# SCH_Record-wav_2025-12-09_1.net
KiCad netlist of a schematic drawn in EasyEDA
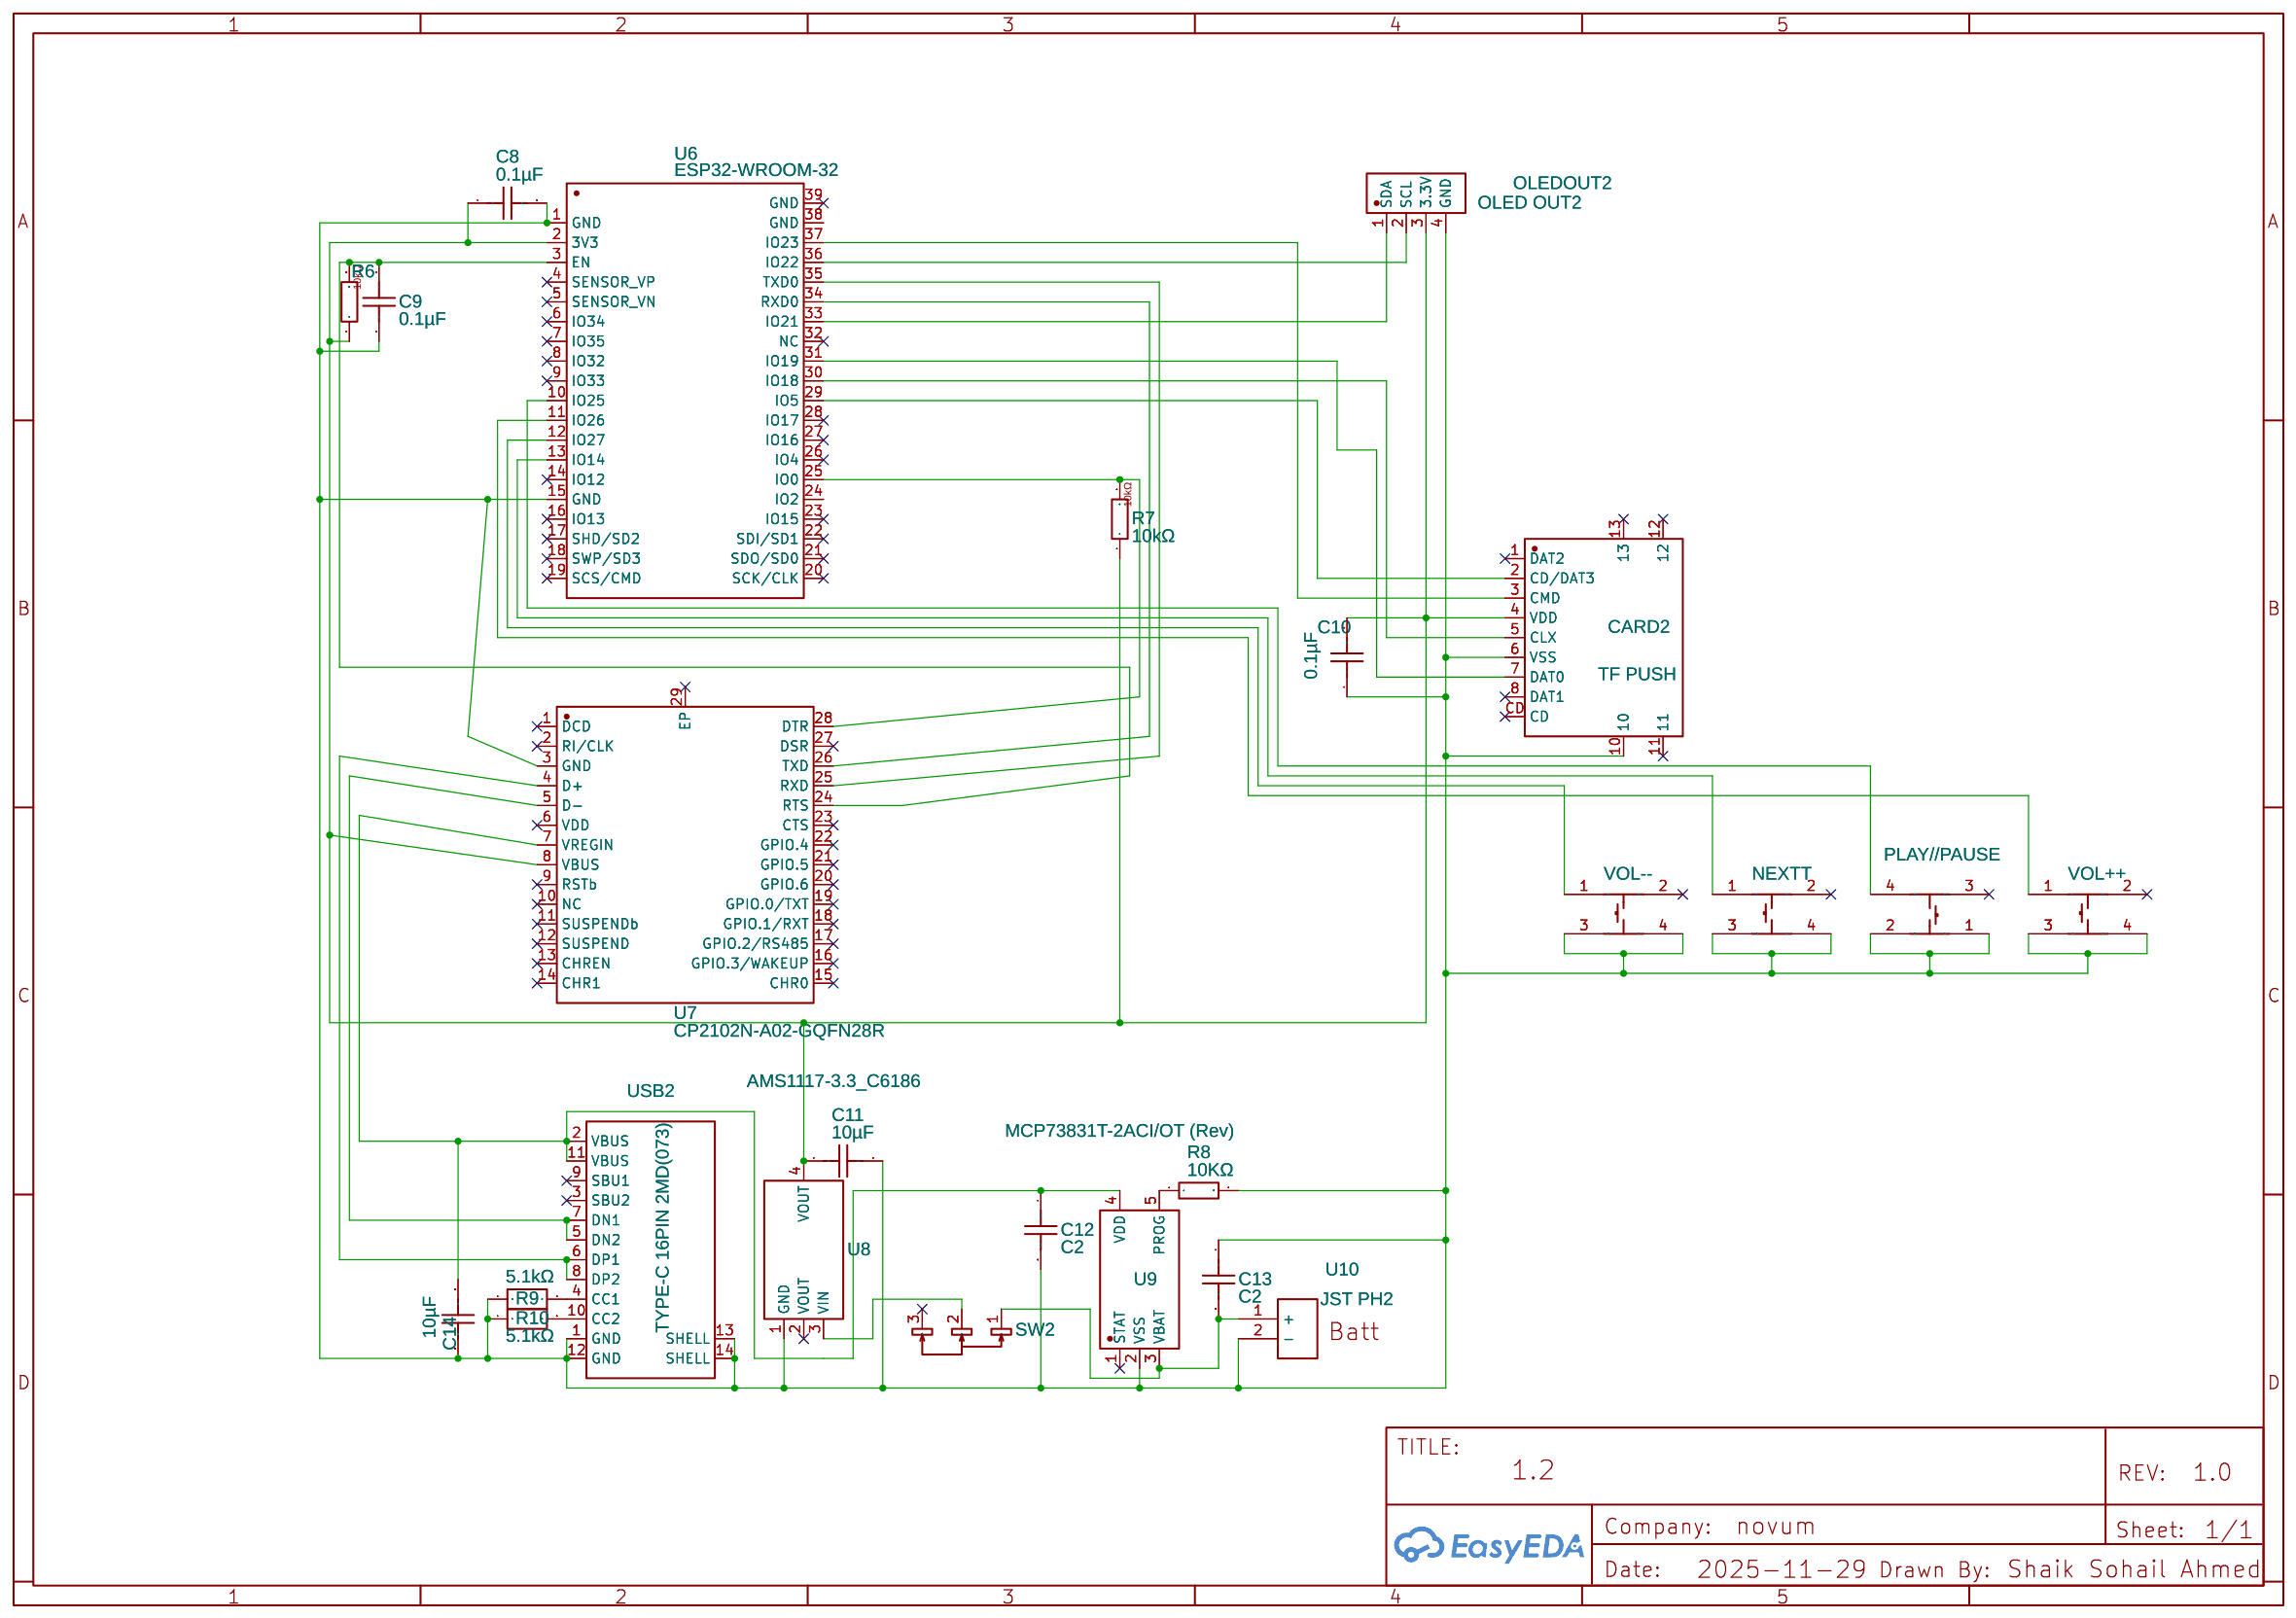
[diagram p0: schematic sheet]

(export (version "E")
  (design (tool "Eeschema 10.0.6"))
  (components
    (comp (ref "C8")
      (value "0.1µF")
      (fields (field (name "Manufacturer Part") "GRM152R60J104ME19D") (field (name "Manufacturer") "muRata"))
      (libsource (lib "") (part "0.1µF_1"))
    )
    (comp (ref "C9")
      (value "0.1µF")
      (fields (field (name "Manufacturer Part") "GRM152R60J104ME19D") (field (name "Manufacturer") "muRata"))
      (libsource (lib "") (part "0.1µF"))
    )
    (comp (ref "C10")
      (value "0.1µF")
      (fields (field (name "Manufacturer Part") "GRM152R60J104ME19D") (field (name "Manufacturer") "muRata"))
      (libsource (lib "") (part "0.1µF"))
    )
    (comp (ref "C11")
      (value "10µF")
      (fields
        (field (name "Manufacturer Part") "CL10A106MA8NRNC")
        (field (name "Manufacturer") "Samsung Electro-Mechanics")
      )
      (libsource (lib "") (part "CL10A106MA8NRNC_1"))
    )
    (comp (ref "C12")
      (value "C2")
      (fields (field (name "Manufacturer Part") "08053C105JAT2A") (field (name "Manufacturer") "KYOCERA AVX"))
      (libsource (lib "") (part "08053C105JAT2A"))
    )
    (comp (ref "C13")
      (value "C2")
      (fields (field (name "Manufacturer Part") "08053C105JAT2A") (field (name "Manufacturer") "KYOCERA AVX"))
      (libsource (lib "") (part "08053C105JAT2A"))
    )
    (comp (ref "C14")
      (value "10µF")
      (fields
        (field (name "Manufacturer Part") "CL10A106MA8NRNC")
        (field (name "Manufacturer") "Samsung Electro-Mechanics")
      )
      (libsource (lib "") (part "CL10A106MA8NRNC"))
    )
    (comp (ref "CARD2")
      (value "TF PUSH")
      (fields (field (name "Manufacturer") "SHOU HAN(首韩)"))
      (libsource (lib "") (part "TF PUSH"))
    )
    (comp (ref "NEXTT")
      (value "TS-1002S-07026C")
      (fields (field (name "Manufacturer") "XUNPU(讯普)"))
      (libsource (lib "") (part "TS-1002S-07026C_2"))
    )
    (comp (ref "OLEDOUT2") (value "OLED OUT2") (libsource (lib "") (part "Solder_Pad_4")))
    (comp (ref "PLAY//PAUSE")
      (value "TS-1002S-07026C")
      (fields (field (name "Manufacturer") "XUNPU(讯普)"))
      (libsource (lib "") (part "TS-1002S-07026C_3"))
    )
    (comp (ref "R6") (value "10kΩ") (libsource (lib "") (part "10kΩ")))
    (comp (ref "R7") (value "10kΩ") (libsource (lib "") (part "10kΩ")))
    (comp (ref "R8")
      (value "10KΩ")
      (fields (field (name "Manufacturer Part") "CFR0W4J0103A50") (field (name "Manufacturer") "UniOhm"))
      (libsource (lib "") (part "10KΩ"))
    )
    (comp (ref "R9")
      (value "5.1kΩ")
      (fields (field (name "Manufacturer Part") "FRC1206F5101TS") (field (name "Manufacturer") "FOJAN(富捷)"))
      (libsource (lib "") (part "5.1KΩ 1/4W ±1% SMD"))
    )
    (comp (ref "R10")
      (value "5.1kΩ")
      (fields (field (name "Manufacturer Part") "FRC1206F5101TS") (field (name "Manufacturer") "FOJAN(富捷)"))
      (libsource (lib "") (part "5.1KΩ 1/4W ±1% SMD"))
    )
    (comp (ref "SW2")
      (value "MST-12D18G4 SPDT SLIDE SWITCH")
      (fields
        (field (name "Manufacturer Part") "MST-12D18G4 SPDT Slide Switch")
        (field (name "Manufacturer") "SHOU HAN(首韩)")
      )
      (libsource (lib "") (part "MST-12D18G4 SPDT SLIDE SWITCH"))
    )
    (comp (ref "U6")
      (value "ESP32-WROOM-32")
      (fields
        (field (name "Manufacturer Part") "ESP32-WROOM-32-N4")
        (field (name "Manufacturer") "ESPRESSIF(乐鑫)")
      )
      (libsource (lib "") (part "ESP32-WROOM-32"))
    )
    (comp (ref "U7")
      (value "CP2102N-A02-GQFN28R")
      (fields (field (name "Manufacturer") "SKYWORKS/SILICON LABS(芯科)"))
      (libsource (lib "") (part "CP2102N-A02-GQFN28R"))
    )
    (comp (ref "U8")
      (value "AMS1117-3.3_C6186")
      (fields (field (name "Manufacturer Part") "AMS1117-3.3") (field (name "Manufacturer") "AMS"))
      (libsource (lib "") (part "AMS1117-3.3_C6186"))
    )
    (comp (ref "U9")
      (value "MCP73831T-2ACI/OT (Rev)")
      (fields
        (field (name "Manufacturer Part") "MCP73831T-2ACI/OT")
        (field (name "Manufacturer") "MICROCHIP(美国微芯)")
      )
      (libsource (lib "") (part "MCP73831T-2ACI/OT (Rev)"))
    )
    (comp (ref "U10") (value "JST PH2") (libsource (lib "") (part "JST PH2")))
    (comp (ref "USB2")
      (value "TYPE-C 16PIN 2MD(073)")
      (fields (field (name "Manufacturer") "SHOU HAN(首韩)"))
      (libsource (lib "") (part "TYPE-C 16PIN 2MD(073)"))
    )
    (comp (ref "VOL++")
      (value "TS-1002S-07026C")
      (fields (field (name "Manufacturer") "XUNPU(讯普)"))
      (libsource (lib "") (part "TS-1002S-07026C_1"))
    )
    (comp (ref "VOL--")
      (value "TS-1002S-07026C")
      (fields (field (name "Manufacturer") "XUNPU(讯普)"))
      (libsource (lib "") (part "TS-1002S-07026C"))
    )
  )
  (nets
    (net (code "1") (name "Net-(CARD2-CD{slash}DAT3)") (class "Default")
      (node (ref "CARD2") (pin "2") (pinfunction "CD/DAT3_2") (pintype "unspecified"))
      (node (ref "U6") (pin "29") (pinfunction "IO5_29") (pintype "unspecified"))
    )
    (net (code "2") (name "Net-(CARD2-CLX)") (class "Default")
      (node (ref "CARD2") (pin "5") (pinfunction "CLX_5") (pintype "unspecified"))
      (node (ref "U6") (pin "30") (pinfunction "IO18_30") (pintype "unspecified"))
    )
    (net (code "3") (name "Net-(CARD2-CMD)") (class "Default")
      (node (ref "CARD2") (pin "3") (pinfunction "CMD_3") (pintype "unspecified"))
      (node (ref "U6") (pin "37") (pinfunction "IO23_37") (pintype "unspecified"))
    )
    (net (code "4") (name "Net-(CARD2-DAT0)") (class "Default")
      (node (ref "CARD2") (pin "7") (pinfunction "DAT0_7") (pintype "unspecified"))
      (node (ref "U6") (pin "31") (pinfunction "IO19_31") (pintype "unspecified"))
    )
    (net (code "5") (name "Net-(CARD2-VDD)") (class "Default")
      (node (ref "C10") (pin "2") (pinfunction "2_2") (pintype "unspecified"))
      (node (ref "C11") (pin "1") (pinfunction "1_1") (pintype "unspecified"))
      (node (ref "C8") (pin "1") (pinfunction "1_1") (pintype "unspecified"))
      (node (ref "CARD2") (pin "4") (pinfunction "VDD_4") (pintype "unspecified"))
      (node (ref "OLEDOUT2") (pin "3") (pinfunction "3.3V_3") (pintype "unspecified"))
      (node (ref "R6") (pin "1") (pinfunction "1_1") (pintype "unspecified"))
      (node (ref "R7") (pin "1") (pinfunction "1_1") (pintype "unspecified"))
      (node (ref "U6") (pin "2") (pinfunction "3V3_2") (pintype "unspecified"))
      (node (ref "U7") (pin "8") (pinfunction "VBUS_8") (pintype "unspecified"))
      (node (ref "U8") (pin "4") (pinfunction "VOUT_4") (pintype "unspecified"))
    )
    (net (code "6") (name "Net-(CARD2-VSS)") (class "Default")
      (node (ref "C10") (pin "1") (pinfunction "1_1") (pintype "unspecified"))
      (node (ref "C11") (pin "2") (pinfunction "2_2") (pintype "unspecified"))
      (node (ref "C12") (pin "2") (pinfunction "2_2") (pintype "unspecified"))
      (node (ref "C13") (pin "1") (pinfunction "1_1") (pintype "unspecified"))
      (node (ref "C14") (pin "2") (pinfunction "2_2") (pintype "unspecified"))
      (node (ref "C8") (pin "2") (pinfunction "2_2") (pintype "unspecified"))
      (node (ref "C9") (pin "1") (pinfunction "1_1") (pintype "unspecified"))
      (node (ref "CARD2") (pin "10") (pinfunction "10_10") (pintype "unspecified"))
      (node (ref "CARD2") (pin "6") (pinfunction "VSS_6") (pintype "unspecified"))
      (node (ref "NEXTT") (pin "3") (pinfunction "3_3") (pintype "unspecified"))
      (node (ref "NEXTT") (pin "4") (pinfunction "4_4") (pintype "unspecified"))
      (node (ref "OLEDOUT2") (pin "4") (pinfunction "GND_4") (pintype "unspecified"))
      (node (ref "PLAY//PAUSE") (pin "1") (pinfunction "1_1") (pintype "unspecified"))
      (node (ref "PLAY//PAUSE") (pin "2") (pinfunction "2_2") (pintype "unspecified"))
      (node (ref "R10") (pin "1") (pinfunction "1_1") (pintype "unspecified"))
      (node (ref "R8") (pin "2") (pinfunction "2_2") (pintype "input"))
      (node (ref "R9") (pin "1") (pinfunction "1_1") (pintype "unspecified"))
      (node (ref "U10") (pin "2") (pinfunction "-_2") (pintype "unspecified"))
      (node (ref "U6") (pin "1") (pinfunction "GND_1") (pintype "unspecified"))
      (node (ref "U6") (pin "15") (pinfunction "GND_15") (pintype "unspecified"))
      (node (ref "U7") (pin "3") (pinfunction "GND_3") (pintype "unspecified"))
      (node (ref "U8") (pin "1") (pinfunction "GND_1") (pintype "unspecified"))
      (node (ref "U9") (pin "2") (pinfunction "VSS_2") (pintype "unspecified"))
      (node (ref "USB2") (pin "1") (pinfunction "GND_1") (pintype "unspecified"))
      (node (ref "USB2") (pin "12") (pinfunction "GND_12") (pintype "unspecified"))
      (node (ref "USB2") (pin "13") (pinfunction "SHELL_13") (pintype "unspecified"))
      (node (ref "USB2") (pin "14") (pinfunction "SHELL_14") (pintype "unspecified"))
      (node (ref "VOL++") (pin "3") (pinfunction "3_3") (pintype "unspecified"))
      (node (ref "VOL++") (pin "4") (pinfunction "4_4") (pintype "unspecified"))
      (node (ref "VOL--") (pin "3") (pinfunction "3_3") (pintype "unspecified"))
      (node (ref "VOL--") (pin "4") (pinfunction "4_4") (pintype "unspecified"))
    )
    (net (code "7") (name "Net-(OLEDOUT2-SCL)") (class "Default")
      (node (ref "OLEDOUT2") (pin "2") (pinfunction "SCL_2") (pintype "unspecified"))
      (node (ref "U6") (pin "36") (pinfunction "IO22_36") (pintype "unspecified"))
    )
    (net (code "8") (name "Net-(OLEDOUT2-SDA)") (class "Default")
      (node (ref "OLEDOUT2") (pin "1") (pinfunction "SDA_1") (pintype "unspecified"))
      (node (ref "U6") (pin "33") (pinfunction "IO21_33") (pintype "unspecified"))
    )
    (net (code "9") (name "Net-(U6-EN)") (class "Default")
      (node (ref "C9") (pin "2") (pinfunction "2_2") (pintype "unspecified"))
      (node (ref "R6") (pin "2") (pinfunction "2_2") (pintype "unspecified"))
      (node (ref "U6") (pin "3") (pinfunction "EN_3") (pintype "unspecified"))
      (node (ref "U7") (pin "24") (pinfunction "RTS_24") (pintype "unspecified"))
    )
    (net (code "10") (name "Net-(U6-IO0)") (class "Default")
      (node (ref "R7") (pin "2") (pinfunction "2_2") (pintype "unspecified"))
      (node (ref "U6") (pin "25") (pinfunction "IO0_25") (pintype "unspecified"))
      (node (ref "U7") (pin "28") (pinfunction "DTR_28") (pintype "unspecified"))
    )
    (net (code "11") (name "Net-(U6-IO14)") (class "Default")
      (node (ref "NEXTT") (pin "1") (pinfunction "1_1") (pintype "unspecified"))
      (node (ref "U6") (pin "13") (pinfunction "IO14_13") (pintype "unspecified"))
    )
    (net (code "12") (name "Net-(U6-IO25)") (class "Default")
      (node (ref "PLAY//PAUSE") (pin "4") (pinfunction "4_4") (pintype "unspecified"))
      (node (ref "U6") (pin "10") (pinfunction "IO25_10") (pintype "unspecified"))
    )
    (net (code "13") (name "Net-(U6-IO26)") (class "Default")
      (node (ref "U6") (pin "11") (pinfunction "IO26_11") (pintype "unspecified"))
      (node (ref "VOL++") (pin "1") (pinfunction "1_1") (pintype "unspecified"))
    )
    (net (code "14") (name "Net-(U6-IO27)") (class "Default")
      (node (ref "U6") (pin "12") (pinfunction "IO27_12") (pintype "unspecified"))
      (node (ref "VOL--") (pin "1") (pinfunction "1_1") (pintype "unspecified"))
    )
    (net (code "15") (name "Net-(U6-RXD0)") (class "Default")
      (node (ref "U6") (pin "34") (pinfunction "RXD0_34") (pintype "unspecified"))
      (node (ref "U7") (pin "26") (pinfunction "TXD_26") (pintype "unspecified"))
    )
    (net (code "16") (name "Net-(U6-TXD0)") (class "Default")
      (node (ref "U6") (pin "35") (pinfunction "TXD0_35") (pintype "unspecified"))
      (node (ref "U7") (pin "25") (pinfunction "RXD_25") (pintype "unspecified"))
    )
    (net (code "17") (name "Net-(U7-D+)") (class "Default")
      (node (ref "U7") (pin "4") (pinfunction "D+_4") (pintype "unspecified"))
      (node (ref "USB2") (pin "6") (pinfunction "DP1_6") (pintype "unspecified"))
      (node (ref "USB2") (pin "8") (pinfunction "DP2_8") (pintype "unspecified"))
    )
    (net (code "18") (name "Net-(U7-D-)") (class "Default")
      (node (ref "U7") (pin "5") (pinfunction "D-_5") (pintype "unspecified"))
      (node (ref "USB2") (pin "5") (pinfunction "DN2_5") (pintype "unspecified"))
      (node (ref "USB2") (pin "7") (pinfunction "DN1_7") (pintype "unspecified"))
    )
    (net (code "19") (name "Net-(U7-VREGIN)") (class "Default")
      (node (ref "C12") (pin "1") (pinfunction "1_1") (pintype "unspecified"))
      (node (ref "C14") (pin "1") (pinfunction "1_1") (pintype "unspecified"))
      (node (ref "U7") (pin "7") (pinfunction "VREGIN_7") (pintype "unspecified"))
      (node (ref "U9") (pin "4") (pinfunction "VDD_4") (pintype "unspecified"))
      (node (ref "USB2") (pin "11") (pinfunction "VBUS_11") (pintype "unspecified"))
      (node (ref "USB2") (pin "2") (pinfunction "VBUS_2") (pintype "unspecified"))
    )
    (net (code "20") (name "Net-(U8-VIN)") (class "Default")
      (node (ref "SW2") (pin "2") (pinfunction "2_2") (pintype "unspecified"))
      (node (ref "U8") (pin "3") (pinfunction "VIN_3") (pintype "unspecified"))
    )
    (net (code "21") (name "Net-(U9-PROG)") (class "Default")
      (node (ref "R8") (pin "1") (pinfunction "1_1") (pintype "input"))
      (node (ref "U9") (pin "5") (pinfunction "PROG_5") (pintype "unspecified"))
    )
    (net (code "22") (name "Net-(U10-+)") (class "Default")
      (node (ref "C13") (pin "2") (pinfunction "2_2") (pintype "unspecified"))
      (node (ref "SW2") (pin "1") (pinfunction "1_1") (pintype "unspecified"))
      (node (ref "U10") (pin "1") (pinfunction "+_1") (pintype "unspecified"))
      (node (ref "U9") (pin "3") (pinfunction "VBAT_3") (pintype "unspecified"))
    )
    (net (code "23") (name "Net-(USB2-CC1)") (class "Default")
      (node (ref "R9") (pin "2") (pinfunction "2_2") (pintype "unspecified"))
      (node (ref "USB2") (pin "4") (pinfunction "CC1_4") (pintype "unspecified"))
    )
    (net (code "24") (name "Net-(USB2-CC2)") (class "Default")
      (node (ref "R10") (pin "2") (pinfunction "2_2") (pintype "unspecified"))
      (node (ref "USB2") (pin "10") (pinfunction "CC2_10") (pintype "unspecified"))
    )
    (net (code "25") (name "unconnected-(CARD2-DAT1-Pad8)") (class "Default")
      (node (ref "CARD2") (pin "8") (pinfunction "DAT1_8") (pintype "unspecified+no_connect"))
    )
    (net (code "26") (name "unconnected-(CARD2-DAT2-Pad1)") (class "Default")
      (node (ref "CARD2") (pin "1") (pinfunction "DAT2_1") (pintype "unspecified+no_connect"))
    )
    (net (code "27") (name "unconnected-(CARD2-Pad11)") (class "Default")
      (node (ref "CARD2") (pin "11") (pinfunction "11_11") (pintype "unspecified+no_connect"))
    )
    (net (code "28") (name "unconnected-(CARD2-Pad12)") (class "Default")
      (node (ref "CARD2") (pin "12") (pinfunction "12_12") (pintype "unspecified+no_connect"))
    )
    (net (code "29") (name "unconnected-(CARD2-Pad13)") (class "Default")
      (node (ref "CARD2") (pin "13") (pinfunction "13_13") (pintype "unspecified+no_connect"))
    )
    (net (code "30") (name "unconnected-(CARD2-PadCD)") (class "Default")
      (node (ref "CARD2") (pin "CD") (pinfunction "CD_CD") (pintype "unspecified+no_connect"))
    )
    (net (code "31") (name "unconnected-(NEXTT-Pad2)") (class "Default")
      (node (ref "NEXTT") (pin "2") (pinfunction "2_2") (pintype "unspecified+no_connect"))
    )
    (net (code "32") (name "unconnected-(PLAY//PAUSE-Pad3)") (class "Default")
      (node (ref "PLAY//PAUSE") (pin "3") (pinfunction "3_3") (pintype "unspecified+no_connect"))
    )
    (net (code "33") (name "unconnected-(SW2-Pad3)") (class "Default")
      (node (ref "SW2") (pin "3") (pinfunction "3_3") (pintype "unspecified+no_connect"))
    )
    (net (code "34") (name "unconnected-(U6-GND-Pad38)") (class "Default")
      (node (ref "U6") (pin "38") (pinfunction "GND_38") (pintype "unspecified"))
    )
    (net (code "35") (name "unconnected-(U6-GND-Pad39)") (class "Default")
      (node (ref "U6") (pin "39") (pinfunction "GND_39") (pintype "unspecified+no_connect"))
    )
    (net (code "36") (name "unconnected-(U6-IO2-Pad24)") (class "Default")
      (node (ref "U6") (pin "24") (pinfunction "IO2_24") (pintype "unspecified"))
    )
    (net (code "37") (name "unconnected-(U6-IO4-Pad26)") (class "Default")
      (node (ref "U6") (pin "26") (pinfunction "IO4_26") (pintype "unspecified+no_connect"))
    )
    (net (code "38") (name "unconnected-(U6-IO12-Pad14)") (class "Default")
      (node (ref "U6") (pin "14") (pinfunction "IO12_14") (pintype "unspecified+no_connect"))
    )
    (net (code "39") (name "unconnected-(U6-IO13-Pad16)") (class "Default")
      (node (ref "U6") (pin "16") (pinfunction "IO13_16") (pintype "unspecified+no_connect"))
    )
    (net (code "40") (name "unconnected-(U6-IO15-Pad23)") (class "Default")
      (node (ref "U6") (pin "23") (pinfunction "IO15_23") (pintype "unspecified+no_connect"))
    )
    (net (code "41") (name "unconnected-(U6-IO16-Pad27)") (class "Default")
      (node (ref "U6") (pin "27") (pinfunction "IO16_27") (pintype "unspecified+no_connect"))
    )
    (net (code "42") (name "unconnected-(U6-IO17-Pad28)") (class "Default")
      (node (ref "U6") (pin "28") (pinfunction "IO17_28") (pintype "unspecified+no_connect"))
    )
    (net (code "43") (name "unconnected-(U6-IO32-Pad8)") (class "Default")
      (node (ref "U6") (pin "8") (pinfunction "IO32_8") (pintype "unspecified+no_connect"))
    )
    (net (code "44") (name "unconnected-(U6-IO33-Pad9)") (class "Default")
      (node (ref "U6") (pin "9") (pinfunction "IO33_9") (pintype "unspecified+no_connect"))
    )
    (net (code "45") (name "unconnected-(U6-IO34-Pad6)") (class "Default")
      (node (ref "U6") (pin "6") (pinfunction "IO34_6") (pintype "unspecified+no_connect"))
    )
    (net (code "46") (name "unconnected-(U6-IO35-Pad7)") (class "Default")
      (node (ref "U6") (pin "7") (pinfunction "IO35_7") (pintype "unspecified+no_connect"))
    )
    (net (code "47") (name "unconnected-(U6-NC-Pad32)") (class "Default")
      (node (ref "U6") (pin "32") (pinfunction "NC_32") (pintype "unspecified+no_connect"))
    )
    (net (code "48") (name "unconnected-(U6-SCK{slash}CLK-Pad20)") (class "Default")
      (node (ref "U6") (pin "20") (pinfunction "SCK/CLK_20") (pintype "unspecified+no_connect"))
    )
    (net (code "49") (name "unconnected-(U6-SCS{slash}CMD-Pad19)") (class "Default")
      (node (ref "U6") (pin "19") (pinfunction "SCS/CMD_19") (pintype "unspecified+no_connect"))
    )
    (net (code "50") (name "unconnected-(U6-SDI{slash}SD1-Pad22)") (class "Default")
      (node (ref "U6") (pin "22") (pinfunction "SDI/SD1_22") (pintype "unspecified+no_connect"))
    )
    (net (code "51") (name "unconnected-(U6-SDO{slash}SD0-Pad21)") (class "Default")
      (node (ref "U6") (pin "21") (pinfunction "SDO/SD0_21") (pintype "unspecified+no_connect"))
    )
    (net (code "52") (name "unconnected-(U6-SENSOR_VN-Pad5)") (class "Default")
      (node (ref "U6") (pin "5") (pinfunction "SENSOR_VN_5") (pintype "unspecified+no_connect"))
    )
    (net (code "53") (name "unconnected-(U6-SENSOR_VP-Pad4)") (class "Default")
      (node (ref "U6") (pin "4") (pinfunction "SENSOR_VP_4") (pintype "unspecified+no_connect"))
    )
    (net (code "54") (name "unconnected-(U6-SHD{slash}SD2-Pad17)") (class "Default")
      (node (ref "U6") (pin "17") (pinfunction "SHD/SD2_17") (pintype "unspecified+no_connect"))
    )
    (net (code "55") (name "unconnected-(U6-SWP{slash}SD3-Pad18)") (class "Default")
      (node (ref "U6") (pin "18") (pinfunction "SWP/SD3_18") (pintype "unspecified+no_connect"))
    )
    (net (code "56") (name "unconnected-(U7-CHR0-Pad15)") (class "Default")
      (node (ref "U7") (pin "15") (pinfunction "CHR0_15") (pintype "unspecified+no_connect"))
    )
    (net (code "57") (name "unconnected-(U7-CHR1-Pad14)") (class "Default")
      (node (ref "U7") (pin "14") (pinfunction "CHR1_14") (pintype "unspecified+no_connect"))
    )
    (net (code "58") (name "unconnected-(U7-CHREN-Pad13)") (class "Default")
      (node (ref "U7") (pin "13") (pinfunction "CHREN_13") (pintype "unspecified+no_connect"))
    )
    (net (code "59") (name "unconnected-(U7-CTS-Pad23)") (class "Default")
      (node (ref "U7") (pin "23") (pinfunction "CTS_23") (pintype "unspecified+no_connect"))
    )
    (net (code "60") (name "unconnected-(U7-DCD-Pad1)") (class "Default")
      (node (ref "U7") (pin "1") (pinfunction "DCD_1") (pintype "unspecified+no_connect"))
    )
    (net (code "61") (name "unconnected-(U7-DSR-Pad27)") (class "Default")
      (node (ref "U7") (pin "27") (pinfunction "DSR_27") (pintype "unspecified+no_connect"))
    )
    (net (code "62") (name "unconnected-(U7-EP-Pad29)") (class "Default")
      (node (ref "U7") (pin "29") (pinfunction "EP_29") (pintype "unspecified+no_connect"))
    )
    (net (code "63") (name "unconnected-(U7-GPIO.0{slash}TXT-Pad19)") (class "Default")
      (node (ref "U7") (pin "19") (pinfunction "GPIO.0/TXT_19") (pintype "unspecified+no_connect"))
    )
    (net (code "64") (name "unconnected-(U7-GPIO.1{slash}RXT-Pad18)") (class "Default")
      (node (ref "U7") (pin "18") (pinfunction "GPIO.1/RXT_18") (pintype "unspecified+no_connect"))
    )
    (net (code "65") (name "unconnected-(U7-GPIO.2{slash}RS485-Pad17)") (class "Default")
      (node (ref "U7") (pin "17") (pinfunction "GPIO.2/RS485_17") (pintype "unspecified+no_connect"))
    )
    (net (code "66") (name "unconnected-(U7-GPIO.3{slash}WAKEUP-Pad16)") (class "Default")
      (node (ref "U7") (pin "16") (pinfunction "GPIO.3/WAKEUP_16") (pintype "unspecified+no_connect"))
    )
    (net (code "67") (name "unconnected-(U7-GPIO.4-Pad22)") (class "Default")
      (node (ref "U7") (pin "22") (pinfunction "GPIO.4_22") (pintype "unspecified+no_connect"))
    )
    (net (code "68") (name "unconnected-(U7-GPIO.5-Pad21)") (class "Default")
      (node (ref "U7") (pin "21") (pinfunction "GPIO.5_21") (pintype "unspecified+no_connect"))
    )
    (net (code "69") (name "unconnected-(U7-GPIO.6-Pad20)") (class "Default")
      (node (ref "U7") (pin "20") (pinfunction "GPIO.6_20") (pintype "unspecified+no_connect"))
    )
    (net (code "70") (name "unconnected-(U7-NC-Pad10)") (class "Default")
      (node (ref "U7") (pin "10") (pinfunction "NC_10") (pintype "unspecified+no_connect"))
    )
    (net (code "71") (name "unconnected-(U7-RI{slash}CLK-Pad2)") (class "Default")
      (node (ref "U7") (pin "2") (pinfunction "RI/CLK_2") (pintype "unspecified+no_connect"))
    )
    (net (code "72") (name "unconnected-(U7-RSTb-Pad9)") (class "Default")
      (node (ref "U7") (pin "9") (pinfunction "RSTb_9") (pintype "unspecified+no_connect"))
    )
    (net (code "73") (name "unconnected-(U7-SUSPEND-Pad12)") (class "Default")
      (node (ref "U7") (pin "12") (pinfunction "SUSPEND_12") (pintype "unspecified+no_connect"))
    )
    (net (code "74") (name "unconnected-(U7-SUSPENDb-Pad11)") (class "Default")
      (node (ref "U7") (pin "11") (pinfunction "SUSPENDb_11") (pintype "unspecified+no_connect"))
    )
    (net (code "75") (name "unconnected-(U7-VDD-Pad6)") (class "Default")
      (node (ref "U7") (pin "6") (pinfunction "VDD_6") (pintype "unspecified+no_connect"))
    )
    (net (code "76") (name "unconnected-(U8-VOUT-Pad2)") (class "Default")
      (node (ref "U8") (pin "2") (pinfunction "VOUT_2") (pintype "unspecified+no_connect"))
    )
    (net (code "77") (name "unconnected-(U9-STAT-Pad1)") (class "Default")
      (node (ref "U9") (pin "1") (pinfunction "STAT_1") (pintype "unspecified+no_connect"))
    )
    (net (code "78") (name "unconnected-(USB2-SBU1-Pad9)") (class "Default")
      (node (ref "USB2") (pin "9") (pinfunction "SBU1_9") (pintype "unspecified+no_connect"))
    )
    (net (code "79") (name "unconnected-(USB2-SBU2-Pad3)") (class "Default")
      (node (ref "USB2") (pin "3") (pinfunction "SBU2_3") (pintype "unspecified+no_connect"))
    )
    (net (code "80") (name "unconnected-(VOL++-Pad2)") (class "Default")
      (node (ref "VOL++") (pin "2") (pinfunction "2_2") (pintype "unspecified+no_connect"))
    )
    (net (code "81") (name "unconnected-(VOL---Pad2)") (class "Default")
      (node (ref "VOL--") (pin "2") (pinfunction "2_2") (pintype "unspecified+no_connect"))
    )
  )
)
